# mcu_brd.net
KiCad netlist of a schematic drawn in EAGLE
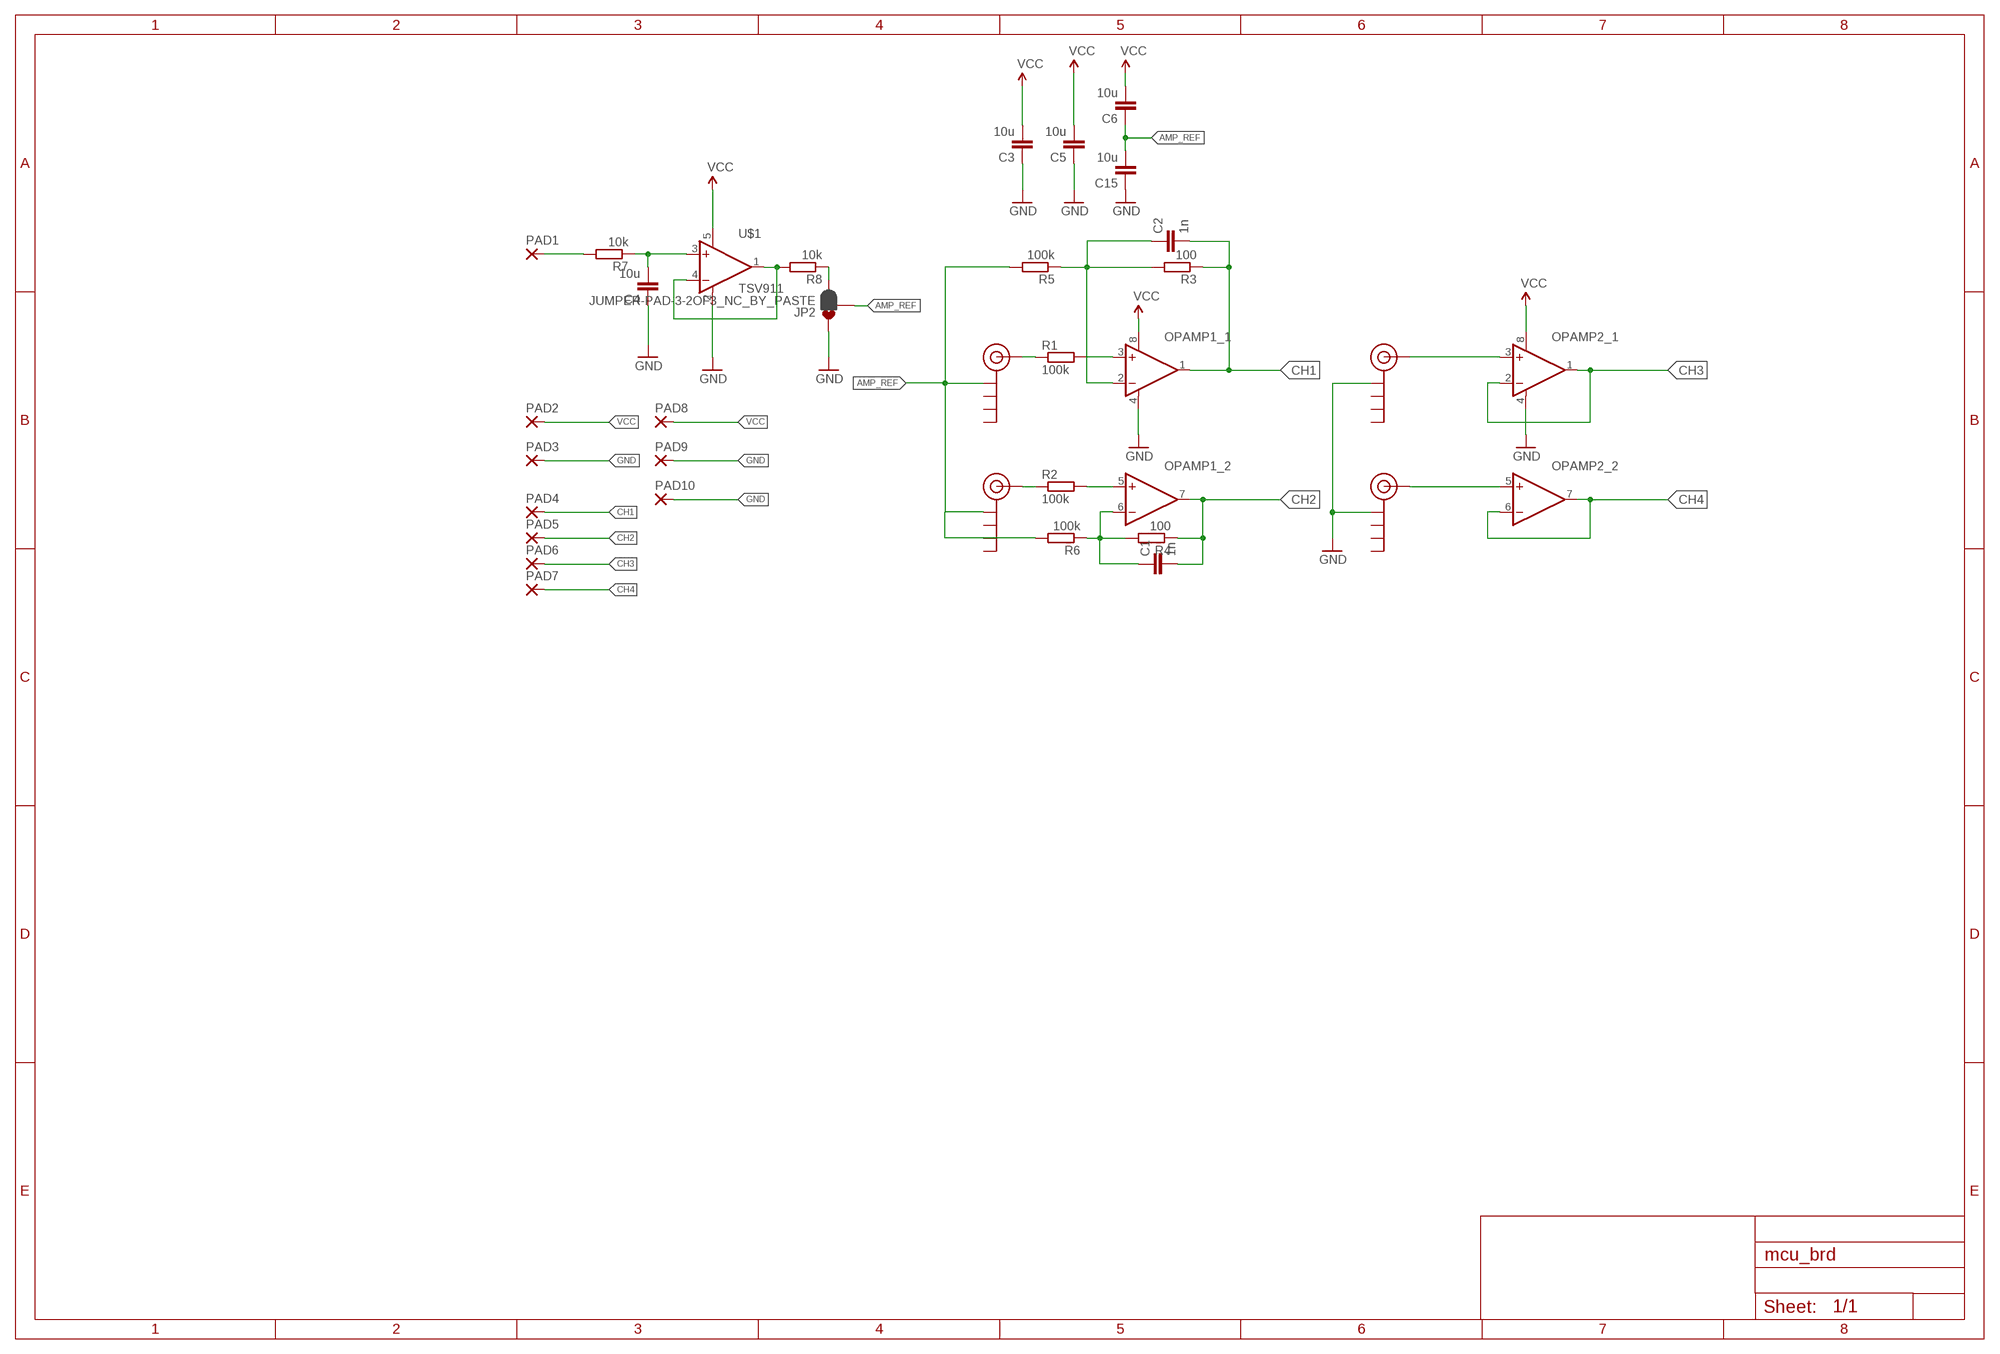
[diagram p0: schematic, sheet 1]

(export (version "E")
  (design (tool "Eeschema 10.0.6"))
  (components
    (comp (ref "C1")
      (value "1n")
      (footprint "eagle-import:C0603")
      (libsource (lib "eagle-import") (part "CC0603"))
    )
    (comp (ref "C2")
      (value "1n")
      (footprint "eagle-import:C0603")
      (libsource (lib "eagle-import") (part "CC0603"))
    )
    (comp (ref "C3")
      (value "10u")
      (footprint "eagle-import:C0805")
      (libsource (lib "eagle-import") (part "CC0805"))
    )
    (comp (ref "C4")
      (value "10u")
      (footprint "eagle-import:C0805")
      (libsource (lib "eagle-import") (part "CC0805"))
    )
    (comp (ref "C5")
      (value "10u")
      (footprint "eagle-import:C0805")
      (libsource (lib "eagle-import") (part "CC0805"))
    )
    (comp (ref "C6")
      (value "10u")
      (footprint "eagle-import:C0805")
      (libsource (lib "eagle-import") (part "CC0805"))
    )
    (comp (ref "C15")
      (value "10u")
      (footprint "eagle-import:C0805")
      (libsource (lib "eagle-import") (part "CC0805"))
    )
    (comp (ref "J$1")
      (value "SMA_EDGE")
      (footprint "eagle-import:SMA-EDGE")
      (libsource (lib "eagle-import") (part "SMA_EDGE"))
    )
    (comp (ref "J$2")
      (value "SMA_EDGE")
      (footprint "eagle-import:SMA-EDGE")
      (libsource (lib "eagle-import") (part "SMA_EDGE"))
    )
    (comp (ref "J$3")
      (value "SMA_EDGE")
      (footprint "eagle-import:SMA-EDGE")
      (libsource (lib "eagle-import") (part "SMA_EDGE"))
    )
    (comp (ref "J$4")
      (value "SMA_EDGE")
      (footprint "eagle-import:SMA-EDGE")
      (libsource (lib "eagle-import") (part "SMA_EDGE"))
    )
    (comp (ref "JP2")
      (value "JUMPER-PAD-3-2OF3_NC_BY_PASTE")
      (footprint "eagle-import:PAD-JUMPER-3-2OF3_NC_BY_PASTE_YES_SILK_FULL_BOX")
      (libsource (lib "eagle-import") (part "JUMPER-PAD-3-2OF3_NC_BY_PASTE"))
    )
    (comp (ref "OPAMP1")
      (value "LMC662")
      (footprint "eagle-import:SO08")
      (libsource (lib "eagle-import") (part "LMC662"))
    )
    (comp (ref "OPAMP2")
      (value "LMC662")
      (footprint "eagle-import:SO08")
      (libsource (lib "eagle-import") (part "LMC662"))
    )
    (comp (ref "PAD1")
      (value "SMD2")
      (footprint "eagle-import:SMD1,27-2,54")
      (libsource (lib "eagle-import") (part "SMD2"))
    )
    (comp (ref "PAD2")
      (value "SMD2")
      (footprint "eagle-import:SMD1,27-2,54")
      (libsource (lib "eagle-import") (part "SMD2"))
    )
    (comp (ref "PAD3")
      (value "SMD2")
      (footprint "eagle-import:SMD1,27-2,54")
      (libsource (lib "eagle-import") (part "SMD2"))
    )
    (comp (ref "PAD4")
      (value "SMD2")
      (footprint "eagle-import:SMD1,27-2,54")
      (libsource (lib "eagle-import") (part "SMD2"))
    )
    (comp (ref "PAD5")
      (value "SMD2")
      (footprint "eagle-import:SMD1,27-2,54")
      (libsource (lib "eagle-import") (part "SMD2"))
    )
    (comp (ref "PAD6")
      (value "SMD2")
      (footprint "eagle-import:SMD1,27-2,54")
      (libsource (lib "eagle-import") (part "SMD2"))
    )
    (comp (ref "PAD7")
      (value "SMD2")
      (footprint "eagle-import:SMD1,27-2,54")
      (libsource (lib "eagle-import") (part "SMD2"))
    )
    (comp (ref "PAD8")
      (value "SMD2")
      (footprint "eagle-import:SMD1,27-2,54")
      (libsource (lib "eagle-import") (part "SMD2"))
    )
    (comp (ref "PAD9")
      (value "SMD2")
      (footprint "eagle-import:SMD1,27-2,54")
      (libsource (lib "eagle-import") (part "SMD2"))
    )
    (comp (ref "PAD10")
      (value "SMD2")
      (footprint "eagle-import:SMD1,27-2,54")
      (libsource (lib "eagle-import") (part "SMD2"))
    )
    (comp (ref "R1")
      (value "100k")
      (footprint "eagle-import:0603")
      (libsource (lib "eagle-import") (part "R0603"))
    )
    (comp (ref "R2")
      (value "100k")
      (footprint "eagle-import:0603")
      (libsource (lib "eagle-import") (part "R0603"))
    )
    (comp (ref "R3")
      (value "100")
      (footprint "eagle-import:0603")
      (libsource (lib "eagle-import") (part "R0603"))
    )
    (comp (ref "R4")
      (value "100")
      (footprint "eagle-import:0603")
      (libsource (lib "eagle-import") (part "R0603"))
    )
    (comp (ref "R5")
      (value "100k")
      (footprint "eagle-import:0603")
      (libsource (lib "eagle-import") (part "R0603"))
    )
    (comp (ref "R6")
      (value "100k")
      (footprint "eagle-import:0603")
      (libsource (lib "eagle-import") (part "R0603"))
    )
    (comp (ref "R7")
      (value "10k")
      (footprint "eagle-import:0603")
      (libsource (lib "eagle-import") (part "R0603"))
    )
    (comp (ref "R8")
      (value "10k")
      (footprint "eagle-import:0603")
      (libsource (lib "eagle-import") (part "R0603"))
    )
    (comp (ref "U$1")
      (value "TSV911")
      (footprint "eagle-import:SOT23-5L")
      (libsource (lib "eagle-import") (part "TSV911"))
    )
  )
  (nets
    (net (code "1") (name "AMP_REF") (class "Default")
      (node (ref "C15") (pin "2") (pinfunction "2_2") (pintype "passive"))
      (node (ref "C6") (pin "1") (pinfunction "1_1") (pintype "passive"))
      (node (ref "J$1") (pin "GND@0") (pinfunction "GND_GND@0") (pintype "bidirectional"))
      (node (ref "J$2") (pin "GND@0") (pinfunction "GND_GND@0") (pintype "bidirectional"))
      (node (ref "JP2") (pin "2") (pinfunction "2_2") (pintype "passive"))
      (node (ref "R5") (pin "2") (pinfunction "2_2") (pintype "passive"))
      (node (ref "R6") (pin "2") (pinfunction "2_2") (pintype "passive"))
    )
    (net (code "2") (name "CH1") (class "Default")
      (node (ref "C2") (pin "2") (pinfunction "2_2") (pintype "passive"))
      (node (ref "OPAMP1") (pin "1") (pinfunction "OUT_1") (pintype "output"))
      (node (ref "PAD4") (pin "1") (pinfunction "P_1") (pintype "passive"))
      (node (ref "R3") (pin "1") (pinfunction "1_1") (pintype "passive"))
    )
    (net (code "3") (name "CH2") (class "Default")
      (node (ref "C1") (pin "2") (pinfunction "2_2") (pintype "passive"))
      (node (ref "OPAMP1") (pin "7") (pinfunction "OUT_7") (pintype "output"))
      (node (ref "PAD5") (pin "1") (pinfunction "P_1") (pintype "passive"))
      (node (ref "R4") (pin "1") (pinfunction "1_1") (pintype "passive"))
    )
    (net (code "4") (name "CH3") (class "Default")
      (node (ref "OPAMP2") (pin "1") (pinfunction "OUT_1") (pintype "output"))
      (node (ref "OPAMP2") (pin "2") (pinfunction "-IN_2") (pintype "input"))
      (node (ref "PAD6") (pin "1") (pinfunction "P_1") (pintype "passive"))
    )
    (net (code "5") (name "CH4") (class "Default")
      (node (ref "OPAMP2") (pin "6") (pinfunction "-IN_6") (pintype "input"))
      (node (ref "OPAMP2") (pin "7") (pinfunction "OUT_7") (pintype "output"))
      (node (ref "PAD7") (pin "1") (pinfunction "P_1") (pintype "passive"))
    )
    (net (code "6") (name "GND") (class "Default")
      (node (ref "C15") (pin "1") (pinfunction "1_1") (pintype "passive"))
      (node (ref "C3") (pin "1") (pinfunction "1_1") (pintype "passive"))
      (node (ref "C4") (pin "1") (pinfunction "1_1") (pintype "passive"))
      (node (ref "C5") (pin "1") (pinfunction "1_1") (pintype "passive"))
      (node (ref "J$3") (pin "GND@0") (pinfunction "GND_GND@0") (pintype "bidirectional"))
      (node (ref "J$4") (pin "GND@0") (pinfunction "GND_GND@0") (pintype "bidirectional"))
      (node (ref "JP2") (pin "1") (pinfunction "1_1") (pintype "passive"))
      (node (ref "OPAMP1") (pin "4") (pinfunction "V-_4") (pintype "power_in"))
      (node (ref "OPAMP2") (pin "4") (pinfunction "V-_4") (pintype "power_in"))
      (node (ref "PAD10") (pin "1") (pinfunction "P_1") (pintype "passive"))
      (node (ref "PAD3") (pin "1") (pinfunction "P_1") (pintype "passive"))
      (node (ref "PAD9") (pin "1") (pinfunction "P_1") (pintype "passive"))
      (node (ref "U$1") (pin "2") (pinfunction "V-_2") (pintype "power_in"))
    )
    (net (code "7") (name "Net-(J$1-SIGNAL)") (class "Default")
      (node (ref "J$1") (pin "SIG") (pinfunction "SIGNAL_SIG") (pintype "bidirectional"))
      (node (ref "R1") (pin "1") (pinfunction "1_1") (pintype "passive"))
    )
    (net (code "8") (name "Net-(J$2-SIGNAL)") (class "Default")
      (node (ref "J$2") (pin "SIG") (pinfunction "SIGNAL_SIG") (pintype "bidirectional"))
      (node (ref "R2") (pin "1") (pinfunction "1_1") (pintype "passive"))
    )
    (net (code "9") (name "Net-(J$3-SIGNAL)") (class "Default")
      (node (ref "J$3") (pin "SIG") (pinfunction "SIGNAL_SIG") (pintype "bidirectional"))
      (node (ref "OPAMP2") (pin "3") (pinfunction "+IN_3") (pintype "input"))
    )
    (net (code "10") (name "Net-(J$4-SIGNAL)") (class "Default")
      (node (ref "J$4") (pin "SIG") (pinfunction "SIGNAL_SIG") (pintype "bidirectional"))
      (node (ref "OPAMP2") (pin "5") (pinfunction "+IN_5") (pintype "input"))
    )
    (net (code "11") (name "Net-(JP2-Pad3)") (class "Default")
      (node (ref "JP2") (pin "3") (pinfunction "3_3") (pintype "passive"))
      (node (ref "R8") (pin "1") (pinfunction "1_1") (pintype "passive"))
    )
    (net (code "12") (name "Net-(OPAMP1A-+IN)") (class "Default")
      (node (ref "OPAMP1") (pin "3") (pinfunction "+IN_3") (pintype "input"))
      (node (ref "R1") (pin "2") (pinfunction "2_2") (pintype "passive"))
    )
    (net (code "13") (name "Net-(OPAMP1A--IN)") (class "Default")
      (node (ref "C2") (pin "1") (pinfunction "1_1") (pintype "passive"))
      (node (ref "OPAMP1") (pin "2") (pinfunction "-IN_2") (pintype "input"))
      (node (ref "R3") (pin "2") (pinfunction "2_2") (pintype "passive"))
      (node (ref "R5") (pin "1") (pinfunction "1_1") (pintype "passive"))
    )
    (net (code "14") (name "Net-(OPAMP1B-+IN)") (class "Default")
      (node (ref "OPAMP1") (pin "5") (pinfunction "+IN_5") (pintype "input"))
      (node (ref "R2") (pin "2") (pinfunction "2_2") (pintype "passive"))
    )
    (net (code "15") (name "Net-(OPAMP1B--IN)") (class "Default")
      (node (ref "C1") (pin "1") (pinfunction "1_1") (pintype "passive"))
      (node (ref "OPAMP1") (pin "6") (pinfunction "-IN_6") (pintype "input"))
      (node (ref "R4") (pin "2") (pinfunction "2_2") (pintype "passive"))
      (node (ref "R6") (pin "1") (pinfunction "1_1") (pintype "passive"))
    )
    (net (code "16") (name "Net-(PAD1-P)") (class "Default")
      (node (ref "PAD1") (pin "1") (pinfunction "P_1") (pintype "passive"))
      (node (ref "R7") (pin "2") (pinfunction "2_2") (pintype "passive"))
    )
    (net (code "17") (name "Net-(U$1-+IN)") (class "Default")
      (node (ref "C4") (pin "2") (pinfunction "2_2") (pintype "passive"))
      (node (ref "R7") (pin "1") (pinfunction "1_1") (pintype "passive"))
      (node (ref "U$1") (pin "3") (pinfunction "+IN_3") (pintype "input"))
    )
    (net (code "18") (name "Net-(U$1--IN)") (class "Default")
      (node (ref "R8") (pin "2") (pinfunction "2_2") (pintype "passive"))
      (node (ref "U$1") (pin "1") (pinfunction "OUT_1") (pintype "output"))
      (node (ref "U$1") (pin "4") (pinfunction "-IN_4") (pintype "input"))
    )
    (net (code "19") (name "VCC") (class "Default")
      (node (ref "C3") (pin "2") (pinfunction "2_2") (pintype "passive"))
      (node (ref "C5") (pin "2") (pinfunction "2_2") (pintype "passive"))
      (node (ref "C6") (pin "2") (pinfunction "2_2") (pintype "passive"))
      (node (ref "OPAMP1") (pin "8") (pinfunction "V+_8") (pintype "power_in"))
      (node (ref "OPAMP2") (pin "8") (pinfunction "V+_8") (pintype "power_in"))
      (node (ref "PAD2") (pin "1") (pinfunction "P_1") (pintype "passive"))
      (node (ref "PAD8") (pin "1") (pinfunction "P_1") (pintype "passive"))
      (node (ref "U$1") (pin "5") (pinfunction "V+_5") (pintype "power_in"))
    )
    (net (code "20") (name "unconnected-(J$1-GND-PadGND@1)") (class "Default")
      (node (ref "J$1") (pin "GND@1") (pinfunction "GND_GND@1") (pintype "bidirectional"))
    )
    (net (code "21") (name "unconnected-(J$1-GND-PadGND@2)") (class "Default")
      (node (ref "J$1") (pin "GND@2") (pinfunction "GND_GND@2") (pintype "bidirectional"))
    )
    (net (code "22") (name "unconnected-(J$1-GND-PadGND@3)") (class "Default")
      (node (ref "J$1") (pin "GND@3") (pinfunction "GND_GND@3") (pintype "bidirectional"))
    )
    (net (code "23") (name "unconnected-(J$2-GND-PadGND@1)") (class "Default")
      (node (ref "J$2") (pin "GND@1") (pinfunction "GND_GND@1") (pintype "bidirectional"))
    )
    (net (code "24") (name "unconnected-(J$2-GND-PadGND@2)") (class "Default")
      (node (ref "J$2") (pin "GND@2") (pinfunction "GND_GND@2") (pintype "bidirectional"))
    )
    (net (code "25") (name "unconnected-(J$2-GND-PadGND@3)") (class "Default")
      (node (ref "J$2") (pin "GND@3") (pinfunction "GND_GND@3") (pintype "bidirectional"))
    )
    (net (code "26") (name "unconnected-(J$3-GND-PadGND@1)") (class "Default")
      (node (ref "J$3") (pin "GND@1") (pinfunction "GND_GND@1") (pintype "bidirectional"))
    )
    (net (code "27") (name "unconnected-(J$3-GND-PadGND@2)") (class "Default")
      (node (ref "J$3") (pin "GND@2") (pinfunction "GND_GND@2") (pintype "bidirectional"))
    )
    (net (code "28") (name "unconnected-(J$3-GND-PadGND@3)") (class "Default")
      (node (ref "J$3") (pin "GND@3") (pinfunction "GND_GND@3") (pintype "bidirectional"))
    )
    (net (code "29") (name "unconnected-(J$4-GND-PadGND@1)") (class "Default")
      (node (ref "J$4") (pin "GND@1") (pinfunction "GND_GND@1") (pintype "bidirectional"))
    )
    (net (code "30") (name "unconnected-(J$4-GND-PadGND@2)") (class "Default")
      (node (ref "J$4") (pin "GND@2") (pinfunction "GND_GND@2") (pintype "bidirectional"))
    )
    (net (code "31") (name "unconnected-(J$4-GND-PadGND@3)") (class "Default")
      (node (ref "J$4") (pin "GND@3") (pinfunction "GND_GND@3") (pintype "bidirectional"))
    )
  )
)
